# band-motor-feather.net
KiCad netlist of a schematic drawn in EAGLE
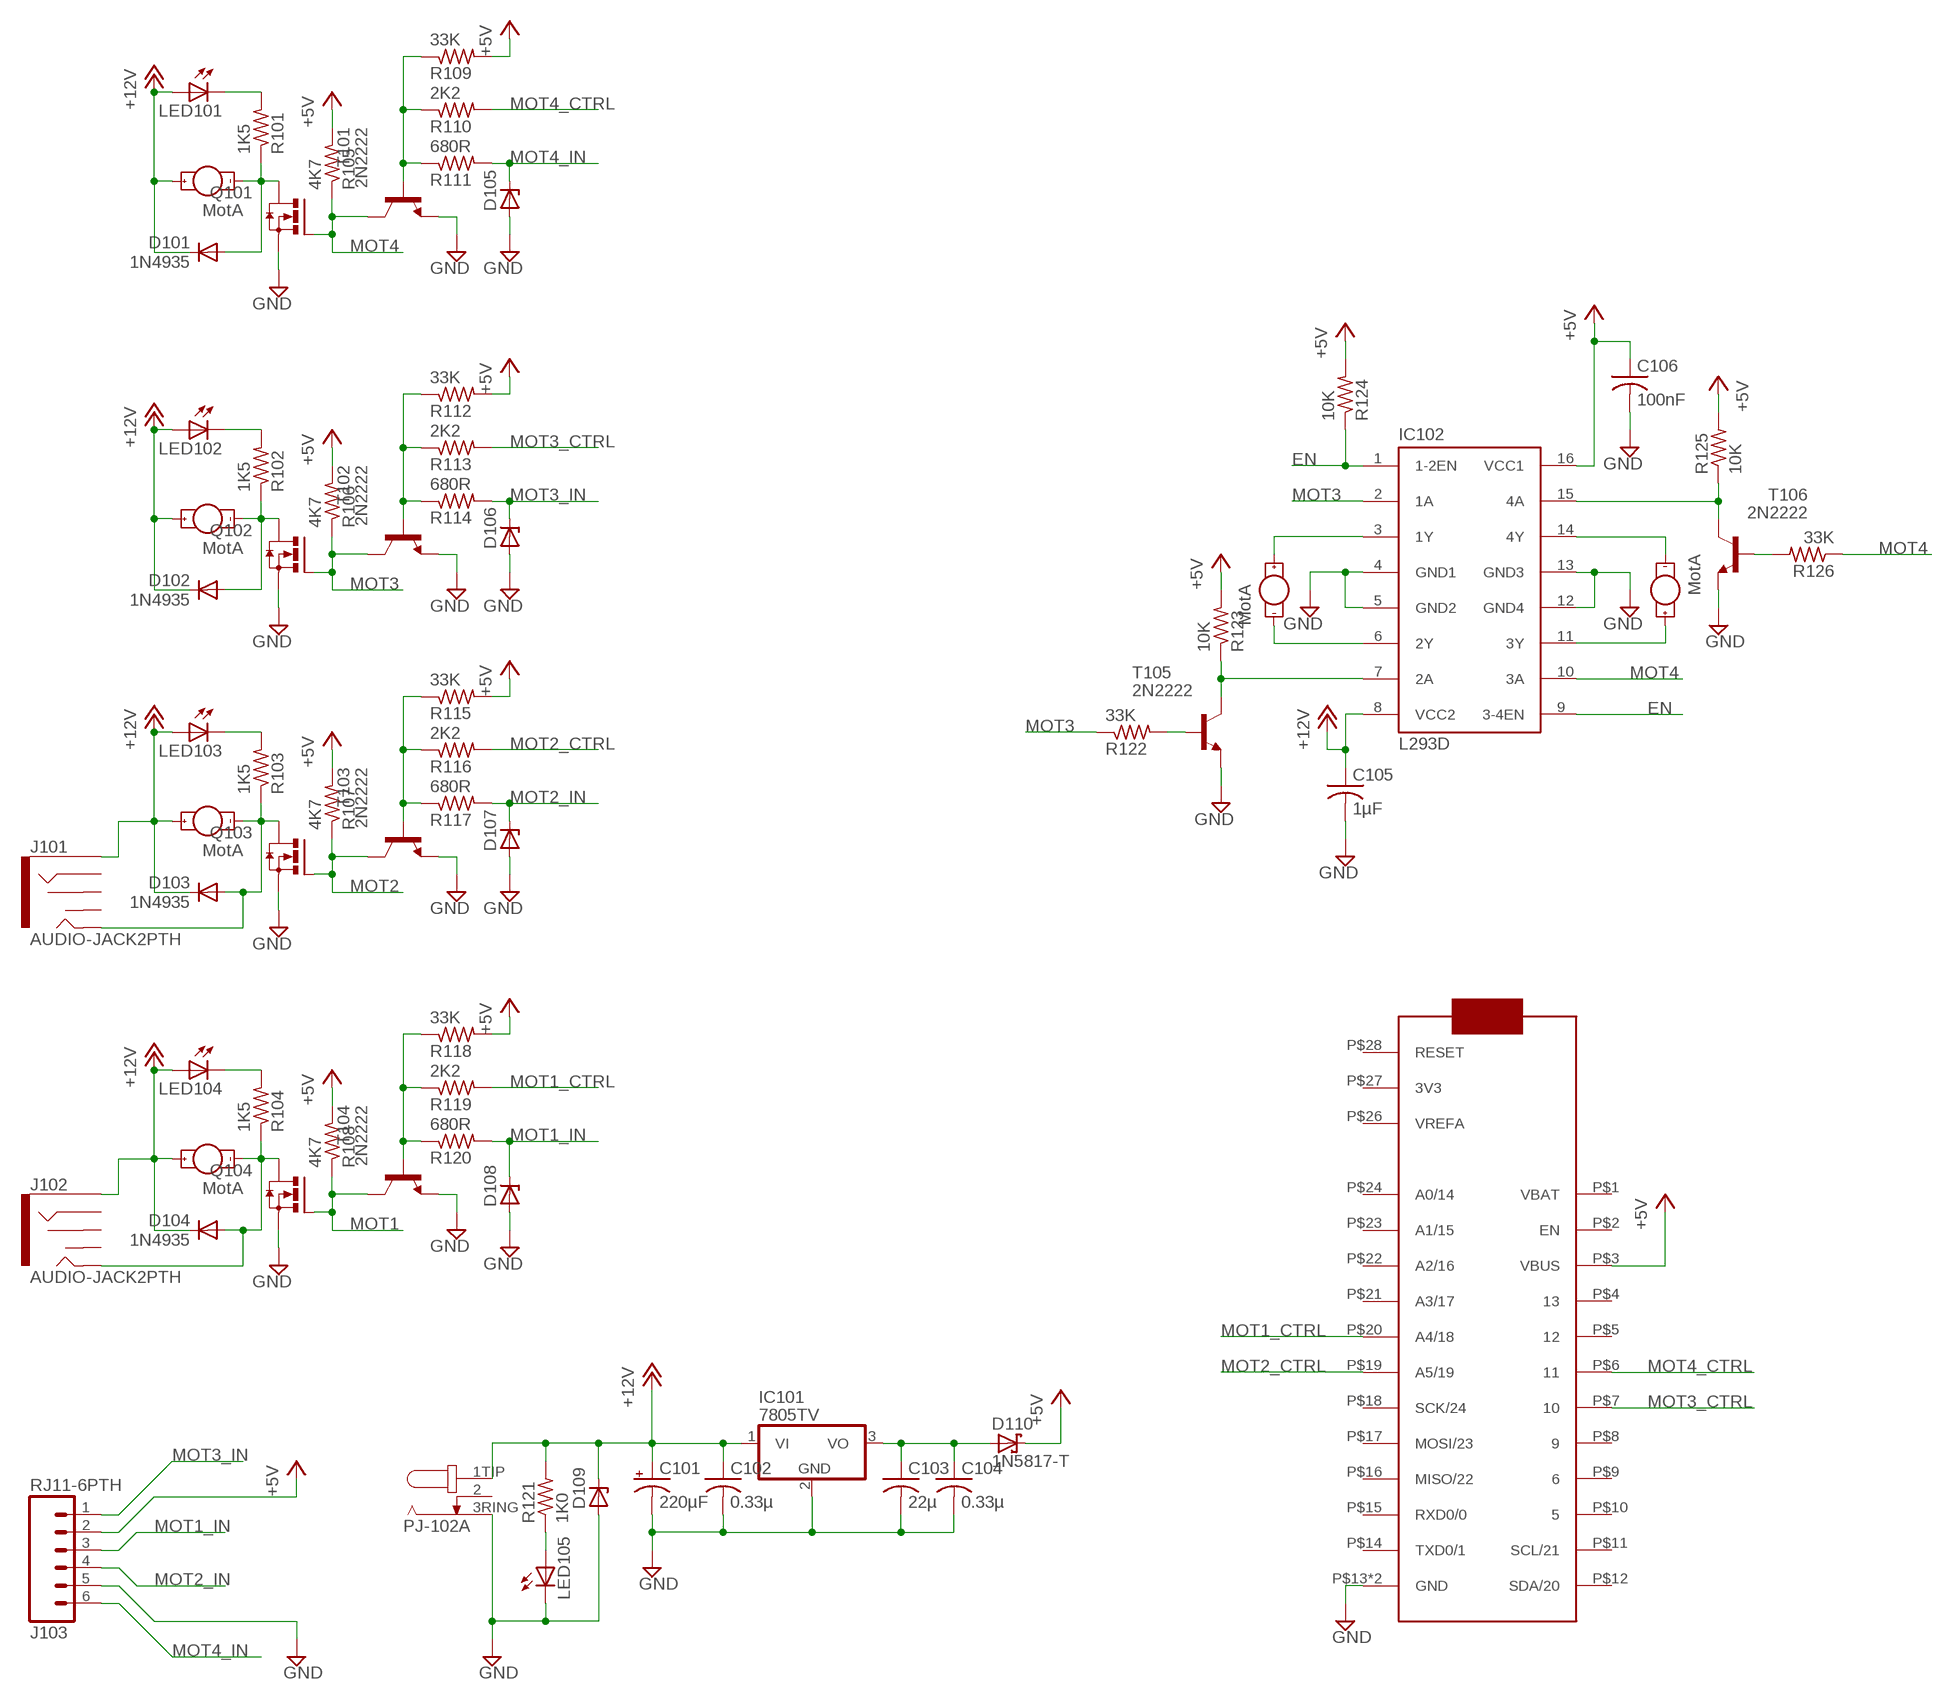
[diagram p0: schematic, sheet 1]

(export (version "E")
  (design (tool "Eeschema 10.0.6"))
  (components
    (comp (ref "C101")
      (value "220µF")
      (footprint "eagle-import:E3,5-8")
      (fields (field (name "MANF") "Panasonic Electronic Components"))
      (libsource (lib "eagle-import") (part "CPOL-USE3.5-8"))
    )
    (comp (ref "C102")
      (value "0.33µ")
      (footprint "eagle-import:C025-050X050")
      (fields (field (name "MANF") "TDK Corporation"))
      (libsource (lib "eagle-import") (part "C-US025-050X050"))
    )
    (comp (ref "C103")
      (value "22µ")
      (footprint "eagle-import:C050-045X075")
      (fields (field (name "MANF") "TDK Corporation"))
      (libsource (lib "eagle-import") (part "C-US050-045X075"))
    )
    (comp (ref "C104")
      (value "0.33µ")
      (footprint "eagle-import:C025-050X050")
      (fields (field (name "MANF") "TDK Corporation"))
      (libsource (lib "eagle-import") (part "C-US025-050X050"))
    )
    (comp (ref "C105")
      (value "1µF")
      (footprint "eagle-import:C025-025X050")
      (fields (field (name "MANF") "TDK Corporation"))
      (libsource (lib "eagle-import") (part "C-US025-025X050"))
    )
    (comp (ref "C106")
      (value "100nF")
      (footprint "eagle-import:C025-025X050")
      (fields (field (name "MANF") "Vishay BC Components"))
      (libsource (lib "eagle-import") (part "C-US025-025X050"))
    )
    (comp (ref "D101")
      (value "1N4935")
      (footprint "eagle-import:DO41-10")
      (fields (field (name "MANF") "Fairchild Semiconductor"))
      (libsource (lib "eagle-import") (part "1N4004"))
    )
    (comp (ref "D102")
      (value "1N4935")
      (footprint "eagle-import:DO41-10")
      (fields (field (name "MANF") "Fairchild Semiconductor"))
      (libsource (lib "eagle-import") (part "1N4004"))
    )
    (comp (ref "D103")
      (value "1N4935")
      (footprint "eagle-import:DO41-10")
      (fields (field (name "MANF") "Fairchild Semiconductor"))
      (libsource (lib "eagle-import") (part "1N4004"))
    )
    (comp (ref "D104")
      (value "1N4935")
      (footprint "eagle-import:DO41-10")
      (fields (field (name "MANF") "Fairchild Semiconductor"))
      (libsource (lib "eagle-import") (part "1N4004"))
    )
    (comp (ref "D105")
      (value "ZENER-DIODEF126-10")
      (footprint "eagle-import:F126Z10")
      (fields (field (name "MANF") "Littelfuse Inc."))
      (libsource (lib "eagle-import") (part "ZENER-DIODEF126-10"))
    )
    (comp (ref "D106")
      (value "ZENER-DIODEF126-10")
      (footprint "eagle-import:F126Z10")
      (fields (field (name "MANF") "Littelfuse Inc."))
      (libsource (lib "eagle-import") (part "ZENER-DIODEF126-10"))
    )
    (comp (ref "D107")
      (value "ZENER-DIODEF126-10")
      (footprint "eagle-import:F126Z10")
      (fields (field (name "MANF") "Littelfuse Inc."))
      (libsource (lib "eagle-import") (part "ZENER-DIODEF126-10"))
    )
    (comp (ref "D108")
      (value "ZENER-DIODEF126-10")
      (footprint "eagle-import:F126Z10")
      (fields (field (name "MANF") "Littelfuse Inc."))
      (libsource (lib "eagle-import") (part "ZENER-DIODEF126-10"))
    )
    (comp (ref "D109")
      (value "ZENER-DIODEF126-10")
      (footprint "eagle-import:F126Z10")
      (fields (field (name "MANF") "Littelfuse Inc."))
      (libsource (lib "eagle-import") (part "ZENER-DIODEF126-10"))
    )
    (comp (ref "D110")
      (value "1N5817-T")
      (footprint "eagle-import:DO41-7.6")
      (fields (field (name "MANF") "Fairchild Semiconductor"))
      (libsource (lib "eagle-import") (part "1N5817-T"))
    )
    (comp (ref "IC101")
      (value "7805TV")
      (footprint "eagle-import:TO220V")
      (fields (field (name "MANF") "Fairchild Semiconductor"))
      (libsource (lib "eagle-import") (part "78TV05"))
    )
    (comp (ref "IC102")
      (value "L293D")
      (footprint "eagle-import:DIL16")
      (fields (field (name "MANF") "Texas Instruments"))
      (libsource (lib "eagle-import") (part "L293D"))
    )
    (comp (ref "IC103")
      (value "FEATHER_M0")
      (footprint "eagle-import:FEATHER_M0")
      (fields (field (name "MANF") "Adafruit Industries LLC"))
      (libsource (lib "eagle-import") (part "FEATHER_M0"))
    )
    (comp (ref "J101")
      (value "AUDIO-JACK2PTH")
      (footprint "eagle-import:AUDIO-JACK")
      (fields (field (name "MANF") "CUI Inc."))
      (libsource (lib "eagle-import") (part "AUDIO-JACK2PTH"))
    )
    (comp (ref "J102")
      (value "AUDIO-JACK2PTH")
      (footprint "eagle-import:AUDIO-JACK")
      (fields (field (name "MANF") "CUI Inc."))
      (libsource (lib "eagle-import") (part "AUDIO-JACK2PTH"))
    )
    (comp (ref "J103")
      (value "RJ11-6PTH")
      (footprint "eagle-import:RJ11-6")
      (fields (field (name "MANF") "Assmann WSW Components"))
      (libsource (lib "eagle-import") (part "RJ11-6PTH"))
    )
    (comp (ref "J104")
      (value "MotA")
      (footprint "eagle-import:1X02_3.5MM_MOT")
      (fields (field (name "MANF") "On Shore Technology Inc."))
      (libsource (lib "eagle-import") (part "1X02_3.5MM_MOT"))
    )
    (comp (ref "J105")
      (value "MotA")
      (footprint "eagle-import:1X02_3.5MM_MOT")
      (fields (field (name "MANF") "On Shore Technology Inc."))
      (libsource (lib "eagle-import") (part "1X02_3.5MM_MOT"))
    )
    (comp (ref "J106")
      (value "MotA")
      (footprint "eagle-import:1X02_3.5MM_MOT")
      (fields (field (name "MANF") "On Shore Technology Inc."))
      (libsource (lib "eagle-import") (part "1X02_3.5MM_MOT"))
    )
    (comp (ref "J107")
      (value "MotA")
      (footprint "eagle-import:1X02_3.5MM_MOT")
      (fields (field (name "MANF") "On Shore Technology Inc."))
      (libsource (lib "eagle-import") (part "1X02_3.5MM_MOT"))
    )
    (comp (ref "J108")
      (value "PJ-102A")
      (footprint "eagle-import:PJ-102A")
      (fields (field (name "MANF") "CUI Inc."))
      (libsource (lib "eagle-import") (part "PJ-102A"))
    )
    (comp (ref "J109")
      (value "MotA")
      (footprint "eagle-import:1X02_3.5MM_MOT")
      (fields (field (name "MANF") "On Shore Technology Inc."))
      (libsource (lib "eagle-import") (part "1X02_3.5MM_MOT"))
    )
    (comp (ref "J110")
      (value "MotA")
      (footprint "eagle-import:1X02_3.5MM_MOT")
      (fields (field (name "MANF") "On Shore Technology Inc."))
      (libsource (lib "eagle-import") (part "1X02_3.5MM_MOT"))
    )
    (comp (ref "LED101")
      (value "LED3MM")
      (footprint "eagle-import:LED3MM")
      (fields (field (name "MANF") "Kingbright"))
      (libsource (lib "eagle-import") (part "LED3MM"))
    )
    (comp (ref "LED102")
      (value "LED3MM")
      (footprint "eagle-import:LED3MM")
      (fields (field (name "MANF") "Kingbright"))
      (libsource (lib "eagle-import") (part "LED3MM"))
    )
    (comp (ref "LED103")
      (value "LED3MM")
      (footprint "eagle-import:LED3MM")
      (fields (field (name "MANF") "Kingbright"))
      (libsource (lib "eagle-import") (part "LED3MM"))
    )
    (comp (ref "LED104")
      (value "LED3MM")
      (footprint "eagle-import:LED3MM")
      (fields (field (name "MANF") "Kingbright"))
      (libsource (lib "eagle-import") (part "LED3MM"))
    )
    (comp (ref "LED105")
      (value "LED5MM")
      (footprint "eagle-import:LED5MM")
      (fields (field (name "MANF") "Kingbright"))
      (libsource (lib "eagle-import") (part "LED5MM"))
    )
    (comp (ref "Q101")
      (value "IRLB8721")
      (footprint "eagle-import:TO220BV")
      (fields (field (name "MANF") "International Rectifier"))
      (libsource (lib "eagle-import") (part "IRLB8721"))
    )
    (comp (ref "Q102")
      (value "IRLB8721")
      (footprint "eagle-import:TO220BV")
      (fields (field (name "MANF") "International Rectifier"))
      (libsource (lib "eagle-import") (part "IRLB8721"))
    )
    (comp (ref "Q103")
      (value "IRLB8721")
      (footprint "eagle-import:TO220BV")
      (fields (field (name "MANF") "International Rectifier"))
      (libsource (lib "eagle-import") (part "IRLB8721"))
    )
    (comp (ref "Q104")
      (value "IRLB8721")
      (footprint "eagle-import:TO220BV")
      (fields (field (name "MANF") "International Rectifier"))
      (libsource (lib "eagle-import") (part "IRLB8721"))
    )
    (comp (ref "R101")
      (value "1K5")
      (footprint "eagle-import:0207_10")
      (fields (field (name "MANF") "Stackpole Electronics Inc"))
      (libsource (lib "eagle-import") (part "R-US_0207/10"))
    )
    (comp (ref "R102")
      (value "1K5")
      (footprint "eagle-import:0207_10")
      (fields (field (name "MANF") "Stackpole Electronics Inc"))
      (libsource (lib "eagle-import") (part "R-US_0207/10"))
    )
    (comp (ref "R103")
      (value "1K5")
      (footprint "eagle-import:0207_10")
      (fields (field (name "MANF") "Stackpole Electronics Inc"))
      (libsource (lib "eagle-import") (part "R-US_0207/10"))
    )
    (comp (ref "R104")
      (value "1K5")
      (footprint "eagle-import:0207_10")
      (fields (field (name "MANF") "Stackpole Electronics Inc"))
      (libsource (lib "eagle-import") (part "R-US_0207/10"))
    )
    (comp (ref "R105")
      (value "4K7")
      (footprint "eagle-import:0207_10")
      (fields (field (name "MANF") "Stackpole Electronics Inc"))
      (libsource (lib "eagle-import") (part "R-US_0207/10"))
    )
    (comp (ref "R106")
      (value "4K7")
      (footprint "eagle-import:0207_10")
      (fields (field (name "MANF") "Stackpole Electronics Inc"))
      (libsource (lib "eagle-import") (part "R-US_0207/10"))
    )
    (comp (ref "R107")
      (value "4K7")
      (footprint "eagle-import:0207_10")
      (fields (field (name "MANF") "Stackpole Electronics Inc"))
      (libsource (lib "eagle-import") (part "R-US_0207/10"))
    )
    (comp (ref "R108")
      (value "4K7")
      (footprint "eagle-import:0207_10")
      (fields (field (name "MANF") "Stackpole Electronics Inc"))
      (libsource (lib "eagle-import") (part "R-US_0207/10"))
    )
    (comp (ref "R109")
      (value "33K")
      (footprint "eagle-import:0207_10")
      (fields (field (name "MANF") "Stackpole Electronics Inc"))
      (libsource (lib "eagle-import") (part "R-US_0207/10"))
    )
    (comp (ref "R110")
      (value "2K2")
      (footprint "eagle-import:0207_10")
      (fields (field (name "MANF") "Stackpole Electronics Inc"))
      (libsource (lib "eagle-import") (part "R-US_0207/10"))
    )
    (comp (ref "R111")
      (value "680R")
      (footprint "eagle-import:0207_10")
      (fields (field (name "MANF") "Stackpole Electronics Inc"))
      (libsource (lib "eagle-import") (part "R-US_0207/10"))
    )
    (comp (ref "R112")
      (value "33K")
      (footprint "eagle-import:0207_10")
      (fields (field (name "MANF") "Stackpole Electronics Inc"))
      (libsource (lib "eagle-import") (part "R-US_0207/10"))
    )
    (comp (ref "R113")
      (value "2K2")
      (footprint "eagle-import:0207_10")
      (fields (field (name "MANF") "Stackpole Electronics Inc"))
      (libsource (lib "eagle-import") (part "R-US_0207/10"))
    )
    (comp (ref "R114")
      (value "680R")
      (footprint "eagle-import:0207_10")
      (fields (field (name "MANF") "Stackpole Electronics Inc"))
      (libsource (lib "eagle-import") (part "R-US_0207/10"))
    )
    (comp (ref "R115")
      (value "33K")
      (footprint "eagle-import:0207_10")
      (fields (field (name "MANF") "Stackpole Electronics Inc"))
      (libsource (lib "eagle-import") (part "R-US_0207/10"))
    )
    (comp (ref "R116")
      (value "2K2")
      (footprint "eagle-import:0207_10")
      (fields (field (name "MANF") "Stackpole Electronics Inc"))
      (libsource (lib "eagle-import") (part "R-US_0207/10"))
    )
    (comp (ref "R117")
      (value "680R")
      (footprint "eagle-import:0207_10")
      (fields (field (name "MANF") "Stackpole Electronics Inc"))
      (libsource (lib "eagle-import") (part "R-US_0207/10"))
    )
    (comp (ref "R118")
      (value "33K")
      (footprint "eagle-import:0207_10")
      (fields (field (name "MANF") "Stackpole Electronics Inc"))
      (libsource (lib "eagle-import") (part "R-US_0207/10"))
    )
    (comp (ref "R119")
      (value "2K2")
      (footprint "eagle-import:0207_10")
      (fields (field (name "MANF") "Stackpole Electronics Inc"))
      (libsource (lib "eagle-import") (part "R-US_0207/10"))
    )
    (comp (ref "R120")
      (value "680R")
      (footprint "eagle-import:0207_10")
      (fields (field (name "MANF") "Stackpole Electronics Inc"))
      (libsource (lib "eagle-import") (part "R-US_0207/10"))
    )
    (comp (ref "R121")
      (value "1K0")
      (footprint "eagle-import:0207_9")
      (fields (field (name "MANF") "Stackpole Electronics Inc."))
      (libsource (lib "eagle-import") (part "R-US_0207/9"))
    )
    (comp (ref "R122")
      (value "33K")
      (footprint "eagle-import:0207_10")
      (fields (field (name "MANF") "Stackpole Electronics Inc"))
      (libsource (lib "eagle-import") (part "R-US_0207/10"))
    )
    (comp (ref "R123")
      (value "10K")
      (footprint "eagle-import:0207_10")
      (fields (field (name "MANF") "Stackpole Electronics Inc"))
      (libsource (lib "eagle-import") (part "R-US_0207/10"))
    )
    (comp (ref "R124")
      (value "10K")
      (footprint "eagle-import:0207_10")
      (fields (field (name "MANF") "Stackpole Electronics Inc"))
      (libsource (lib "eagle-import") (part "R-US_0207/10"))
    )
    (comp (ref "R125")
      (value "10K")
      (footprint "eagle-import:0207_10")
      (fields (field (name "MANF") "Stackpole Electronics Inc"))
      (libsource (lib "eagle-import") (part "R-US_0207/10"))
    )
    (comp (ref "R126")
      (value "33K")
      (footprint "eagle-import:0207_10")
      (fields (field (name "MANF") "Stackpole Electronics Inc"))
      (libsource (lib "eagle-import") (part "R-US_0207/10"))
    )
    (comp (ref "T101")
      (value "2N2222")
      (footprint "eagle-import:TO92-EBC-OVAL")
      (fields (field (name "MANF") "Fairchild Semiconductor"))
      (libsource (lib "eagle-import") (part "2N2222"))
    )
    (comp (ref "T102")
      (value "2N2222")
      (footprint "eagle-import:TO92-EBC-OVAL")
      (fields (field (name "MANF") "Fairchild Semiconductor"))
      (libsource (lib "eagle-import") (part "2N2222"))
    )
    (comp (ref "T103")
      (value "2N2222")
      (footprint "eagle-import:TO92-EBC-OVAL")
      (fields (field (name "MANF") "Fairchild Semiconductor"))
      (libsource (lib "eagle-import") (part "2N2222"))
    )
    (comp (ref "T104")
      (value "2N2222")
      (footprint "eagle-import:TO92-EBC-OVAL")
      (fields (field (name "MANF") "Fairchild Semiconductor"))
      (libsource (lib "eagle-import") (part "2N2222"))
    )
    (comp (ref "T105")
      (value "2N2222")
      (footprint "eagle-import:TO92-EBC-OVAL")
      (fields (field (name "MANF") "Fairchild Semiconductor"))
      (libsource (lib "eagle-import") (part "2N2222"))
    )
    (comp (ref "T106")
      (value "2N2222")
      (footprint "eagle-import:TO92-EBC-OVAL")
      (fields (field (name "MANF") "Fairchild Semiconductor"))
      (libsource (lib "eagle-import") (part "2N2222"))
    )
  )
  (nets
    (net (code "1") (name "+5V") (class "Default")
      (node (ref "C106") (pin "1") (pinfunction "1_1") (pintype "passive"))
      (node (ref "D110") (pin "C") (pinfunction "C_C") (pintype "passive"))
      (node (ref "IC102") (pin "16") (pinfunction "VCC1_16") (pintype "power_in"))
      (node (ref "IC103") (pin "P$3") (pinfunction "VBUS_P$3") (pintype "bidirectional"))
      (node (ref "J103") (pin "2") (pinfunction "2_2") (pintype "passive"))
      (node (ref "R105") (pin "2") (pinfunction "2_2") (pintype "passive"))
      (node (ref "R106") (pin "2") (pinfunction "2_2") (pintype "passive"))
      (node (ref "R107") (pin "2") (pinfunction "2_2") (pintype "passive"))
      (node (ref "R108") (pin "2") (pinfunction "2_2") (pintype "passive"))
      (node (ref "R109") (pin "2") (pinfunction "2_2") (pintype "passive"))
      (node (ref "R112") (pin "2") (pinfunction "2_2") (pintype "passive"))
      (node (ref "R115") (pin "2") (pinfunction "2_2") (pintype "passive"))
      (node (ref "R118") (pin "2") (pinfunction "2_2") (pintype "passive"))
      (node (ref "R123") (pin "2") (pinfunction "2_2") (pintype "passive"))
      (node (ref "R124") (pin "2") (pinfunction "2_2") (pintype "passive"))
      (node (ref "R125") (pin "2") (pinfunction "2_2") (pintype "passive"))
    )
    (net (code "2") (name "+12V") (class "Default")
      (node (ref "C101") (pin "+") (pinfunction "+_+") (pintype "passive"))
      (node (ref "C102") (pin "1") (pinfunction "1_1") (pintype "passive"))
      (node (ref "C105") (pin "1") (pinfunction "1_1") (pintype "passive"))
      (node (ref "D101") (pin "C") (pinfunction "C_C") (pintype "passive"))
      (node (ref "D102") (pin "C") (pinfunction "C_C") (pintype "passive"))
      (node (ref "D103") (pin "C") (pinfunction "C_C") (pintype "passive"))
      (node (ref "D104") (pin "C") (pinfunction "C_C") (pintype "passive"))
      (node (ref "D109") (pin "C") (pinfunction "C_C") (pintype "passive"))
      (node (ref "IC101") (pin "1") (pinfunction "VI_1") (pintype "input"))
      (node (ref "IC102") (pin "8") (pinfunction "VCC2_8") (pintype "power_in"))
      (node (ref "J101") (pin "SLEEVE") (pinfunction "SLEEVE_SLEEVE") (pintype "bidirectional"))
      (node (ref "J102") (pin "SLEEVE") (pinfunction "SLEEVE_SLEEVE") (pintype "bidirectional"))
      (node (ref "J104") (pin "1A") (pinfunction "+_1A") (pintype "bidirectional"))
      (node (ref "J105") (pin "1A") (pinfunction "+_1A") (pintype "bidirectional"))
      (node (ref "J106") (pin "1A") (pinfunction "+_1A") (pintype "bidirectional"))
      (node (ref "J107") (pin "1A") (pinfunction "+_1A") (pintype "bidirectional"))
      (node (ref "J108") (pin "1TIP") (pinfunction "3TIP_1TIP") (pintype "passive"))
      (node (ref "LED101") (pin "A") (pinfunction "A_A") (pintype "passive"))
      (node (ref "LED102") (pin "A") (pinfunction "A_A") (pintype "passive"))
      (node (ref "LED103") (pin "A") (pinfunction "A_A") (pintype "passive"))
      (node (ref "LED104") (pin "A") (pinfunction "A_A") (pintype "passive"))
      (node (ref "R121") (pin "2") (pinfunction "2_2") (pintype "passive"))
    )
    (net (code "3") (name "/EN") (class "Default")
      (node (ref "IC102") (pin "1") (pinfunction "1-2EN_1") (pintype "input"))
      (node (ref "IC102") (pin "9") (pinfunction "3-4EN_9") (pintype "input"))
      (node (ref "R124") (pin "1") (pinfunction "1_1") (pintype "passive"))
    )
    (net (code "4") (name "/MOT1") (class "Default")
      (node (ref "Q104") (pin "G") (pinfunction "G_G") (pintype "passive"))
      (node (ref "R108") (pin "1") (pinfunction "1_1") (pintype "passive"))
      (node (ref "T104") (pin "C") (pinfunction "C_C") (pintype "passive"))
    )
    (net (code "5") (name "/MOT1_CTRL") (class "Default")
      (node (ref "IC103") (pin "P$20") (pinfunction "A4/18_P$20") (pintype "bidirectional"))
      (node (ref "R119") (pin "2") (pinfunction "2_2") (pintype "passive"))
    )
    (net (code "6") (name "/MOT1_IN") (class "Default")
      (node (ref "D108") (pin "C") (pinfunction "C_C") (pintype "passive"))
      (node (ref "J103") (pin "3") (pinfunction "3_3") (pintype "passive"))
      (node (ref "R120") (pin "2") (pinfunction "2_2") (pintype "passive"))
    )
    (net (code "7") (name "/MOT2") (class "Default")
      (node (ref "Q103") (pin "G") (pinfunction "G_G") (pintype "passive"))
      (node (ref "R107") (pin "1") (pinfunction "1_1") (pintype "passive"))
      (node (ref "T103") (pin "C") (pinfunction "C_C") (pintype "passive"))
    )
    (net (code "8") (name "/MOT2_CTRL") (class "Default")
      (node (ref "IC103") (pin "P$19") (pinfunction "A5/19_P$19") (pintype "bidirectional"))
      (node (ref "R116") (pin "2") (pinfunction "2_2") (pintype "passive"))
    )
    (net (code "9") (name "/MOT2_IN") (class "Default")
      (node (ref "D107") (pin "C") (pinfunction "C_C") (pintype "passive"))
      (node (ref "J103") (pin "4") (pinfunction "4_4") (pintype "passive"))
      (node (ref "R117") (pin "2") (pinfunction "2_2") (pintype "passive"))
    )
    (net (code "10") (name "/MOT3") (class "Default")
      (node (ref "IC102") (pin "2") (pinfunction "1A_2") (pintype "input"))
      (node (ref "Q102") (pin "G") (pinfunction "G_G") (pintype "passive"))
      (node (ref "R106") (pin "1") (pinfunction "1_1") (pintype "passive"))
      (node (ref "R122") (pin "1") (pinfunction "1_1") (pintype "passive"))
      (node (ref "T102") (pin "C") (pinfunction "C_C") (pintype "passive"))
    )
    (net (code "11") (name "/MOT3_CTRL") (class "Default")
      (node (ref "IC103") (pin "P$7") (pinfunction "10_P$7") (pintype "bidirectional"))
      (node (ref "R113") (pin "2") (pinfunction "2_2") (pintype "passive"))
    )
    (net (code "12") (name "/MOT3_IN") (class "Default")
      (node (ref "D106") (pin "C") (pinfunction "C_C") (pintype "passive"))
      (node (ref "J103") (pin "1") (pinfunction "1_1") (pintype "passive"))
      (node (ref "R114") (pin "2") (pinfunction "2_2") (pintype "passive"))
    )
    (net (code "13") (name "/MOT4") (class "Default")
      (node (ref "IC102") (pin "10") (pinfunction "3A_10") (pintype "input"))
      (node (ref "Q101") (pin "G") (pinfunction "G_G") (pintype "passive"))
      (node (ref "R105") (pin "1") (pinfunction "1_1") (pintype "passive"))
      (node (ref "R126") (pin "1") (pinfunction "1_1") (pintype "passive"))
      (node (ref "T101") (pin "C") (pinfunction "C_C") (pintype "passive"))
    )
    (net (code "14") (name "/MOT4_CTRL") (class "Default")
      (node (ref "IC103") (pin "P$6") (pinfunction "11_P$6") (pintype "bidirectional"))
      (node (ref "R110") (pin "2") (pinfunction "2_2") (pintype "passive"))
    )
    (net (code "15") (name "/MOT4_IN") (class "Default")
      (node (ref "D105") (pin "C") (pinfunction "C_C") (pintype "passive"))
      (node (ref "J103") (pin "6") (pinfunction "6_6") (pintype "passive"))
      (node (ref "R111") (pin "2") (pinfunction "2_2") (pintype "passive"))
    )
    (net (code "16") (name "GND") (class "Default")
      (node (ref "C101") (pin "-") (pinfunction "-_-") (pintype "passive"))
      (node (ref "C102") (pin "2") (pinfunction "2_2") (pintype "passive"))
      (node (ref "C103") (pin "2") (pinfunction "2_2") (pintype "passive"))
      (node (ref "C104") (pin "2") (pinfunction "2_2") (pintype "passive"))
      (node (ref "C105") (pin "2") (pinfunction "2_2") (pintype "passive"))
      (node (ref "C106") (pin "2") (pinfunction "2_2") (pintype "passive"))
      (node (ref "D105") (pin "A") (pinfunction "A_A") (pintype "passive"))
      (node (ref "D106") (pin "A") (pinfunction "A_A") (pintype "passive"))
      (node (ref "D107") (pin "A") (pinfunction "A_A") (pintype "passive"))
      (node (ref "D108") (pin "A") (pinfunction "A_A") (pintype "passive"))
      (node (ref "D109") (pin "A") (pinfunction "A_A") (pintype "passive"))
      (node (ref "IC101") (pin "2") (pinfunction "GND_2") (pintype "passive"))
      (node (ref "IC102") (pin "12") (pinfunction "GND4_12") (pintype "power_in"))
      (node (ref "IC102") (pin "13") (pinfunction "GND3_13") (pintype "power_in"))
      (node (ref "IC102") (pin "4") (pinfunction "GND1_4") (pintype "power_in"))
      (node (ref "IC102") (pin "5") (pinfunction "GND2_5") (pintype "power_in"))
      (node (ref "IC103") (pin "P$13") (pinfunction "GND_P$13") (pintype "bidirectional"))
      (node (ref "IC103") (pin "P$25") (pinfunction "GND_P$25") (pintype "bidirectional"))
      (node (ref "J103") (pin "5") (pinfunction "5_5") (pintype "passive"))
      (node (ref "J108") (pin "3RING") (pinfunction "1RING_3RING") (pintype "passive"))
      (node (ref "LED105") (pin "K") (pinfunction "C_K") (pintype "passive"))
      (node (ref "Q101") (pin "S") (pinfunction "S_S") (pintype "passive"))
      (node (ref "Q102") (pin "S") (pinfunction "S_S") (pintype "passive"))
      (node (ref "Q103") (pin "S") (pinfunction "S_S") (pintype "passive"))
      (node (ref "Q104") (pin "S") (pinfunction "S_S") (pintype "passive"))
      (node (ref "T101") (pin "E") (pinfunction "E_E") (pintype "passive"))
      (node (ref "T102") (pin "E") (pinfunction "E_E") (pintype "passive"))
      (node (ref "T103") (pin "E") (pinfunction "E_E") (pintype "passive"))
      (node (ref "T104") (pin "E") (pinfunction "E_E") (pintype "passive"))
      (node (ref "T105") (pin "E") (pinfunction "E_E") (pintype "passive"))
      (node (ref "T106") (pin "E") (pinfunction "E_E") (pintype "passive"))
    )
    (net (code "17") (name "Net-(IC101-VO)") (class "Default")
      (node (ref "C103") (pin "1") (pinfunction "1_1") (pintype "passive"))
      (node (ref "C104") (pin "1") (pinfunction "1_1") (pintype "passive"))
      (node (ref "D110") (pin "A") (pinfunction "A_A") (pintype "passive"))
      (node (ref "IC101") (pin "3") (pinfunction "VO_3") (pintype "passive"))
    )
    (net (code "18") (name "Net-(IC102-1Y)") (class "Default")
      (node (ref "IC102") (pin "3") (pinfunction "1Y_3") (pintype "output"))
      (node (ref "J109") (pin "1A") (pinfunction "+_1A") (pintype "bidirectional"))
    )
    (net (code "19") (name "Net-(IC102-2A)") (class "Default")
      (node (ref "IC102") (pin "7") (pinfunction "2A_7") (pintype "input"))
      (node (ref "R123") (pin "1") (pinfunction "1_1") (pintype "passive"))
      (node (ref "T105") (pin "C") (pinfunction "C_C") (pintype "passive"))
    )
    (net (code "20") (name "Net-(IC102-2Y)") (class "Default")
      (node (ref "IC102") (pin "6") (pinfunction "2Y_6") (pintype "output"))
      (node (ref "J109") (pin "2K") (pinfunction "-_2K") (pintype "bidirectional"))
    )
    (net (code "21") (name "Net-(IC102-3Y)") (class "Default")
      (node (ref "IC102") (pin "11") (pinfunction "3Y_11") (pintype "output"))
      (node (ref "J110") (pin "1A") (pinfunction "+_1A") (pintype "bidirectional"))
    )
    (net (code "22") (name "Net-(IC102-4A)") (class "Default")
      (node (ref "IC102") (pin "15") (pinfunction "4A_15") (pintype "input"))
      (node (ref "R125") (pin "1") (pinfunction "1_1") (pintype "passive"))
      (node (ref "T106") (pin "C") (pinfunction "C_C") (pintype "passive"))
    )
    (net (code "23") (name "Net-(IC102-4Y)") (class "Default")
      (node (ref "IC102") (pin "14") (pinfunction "4Y_14") (pintype "output"))
      (node (ref "J110") (pin "2K") (pinfunction "-_2K") (pintype "bidirectional"))
    )
    (net (code "24") (name "Net-(J104--)") (class "Default")
      (node (ref "D101") (pin "A") (pinfunction "A_A") (pintype "passive"))
      (node (ref "J104") (pin "2K") (pinfunction "-_2K") (pintype "bidirectional"))
      (node (ref "Q101") (pin "D") (pinfunction "D_D") (pintype "passive"))
      (node (ref "R101") (pin "1") (pinfunction "1_1") (pintype "passive"))
    )
    (net (code "25") (name "Net-(J105--)") (class "Default")
      (node (ref "D102") (pin "A") (pinfunction "A_A") (pintype "passive"))
      (node (ref "J105") (pin "2K") (pinfunction "-_2K") (pintype "bidirectional"))
      (node (ref "Q102") (pin "D") (pinfunction "D_D") (pintype "passive"))
      (node (ref "R102") (pin "1") (pinfunction "1_1") (pintype "passive"))
    )
    (net (code "26") (name "Net-(J106--)") (class "Default")
      (node (ref "D103") (pin "A") (pinfunction "A_A") (pintype "passive"))
      (node (ref "J101") (pin "TIP") (pinfunction "TIP_TIP") (pintype "bidirectional"))
      (node (ref "J106") (pin "2K") (pinfunction "-_2K") (pintype "bidirectional"))
      (node (ref "Q103") (pin "D") (pinfunction "D_D") (pintype "passive"))
      (node (ref "R103") (pin "1") (pinfunction "1_1") (pintype "passive"))
    )
    (net (code "27") (name "Net-(J107--)") (class "Default")
      (node (ref "D104") (pin "A") (pinfunction "A_A") (pintype "passive"))
      (node (ref "J102") (pin "TIP") (pinfunction "TIP_TIP") (pintype "bidirectional"))
      (node (ref "J107") (pin "2K") (pinfunction "-_2K") (pintype "bidirectional"))
      (node (ref "Q104") (pin "D") (pinfunction "D_D") (pintype "passive"))
      (node (ref "R104") (pin "1") (pinfunction "1_1") (pintype "passive"))
    )
    (net (code "28") (name "Net-(LED101-C)") (class "Default")
      (node (ref "LED101") (pin "K") (pinfunction "C_K") (pintype "passive"))
      (node (ref "R101") (pin "2") (pinfunction "2_2") (pintype "passive"))
    )
    (net (code "29") (name "Net-(LED102-C)") (class "Default")
      (node (ref "LED102") (pin "K") (pinfunction "C_K") (pintype "passive"))
      (node (ref "R102") (pin "2") (pinfunction "2_2") (pintype "passive"))
    )
    (net (code "30") (name "Net-(LED103-C)") (class "Default")
      (node (ref "LED103") (pin "K") (pinfunction "C_K") (pintype "passive"))
      (node (ref "R103") (pin "2") (pinfunction "2_2") (pintype "passive"))
    )
    (net (code "31") (name "Net-(LED104-C)") (class "Default")
      (node (ref "LED104") (pin "K") (pinfunction "C_K") (pintype "passive"))
      (node (ref "R104") (pin "2") (pinfunction "2_2") (pintype "passive"))
    )
    (net (code "32") (name "Net-(LED105-PadA)") (class "Default")
      (node (ref "LED105") (pin "A") (pinfunction "A_A") (pintype "passive"))
      (node (ref "R121") (pin "1") (pinfunction "1_1") (pintype "passive"))
    )
    (net (code "33") (name "Net-(R109-Pad1)") (class "Default")
      (node (ref "R109") (pin "1") (pinfunction "1_1") (pintype "passive"))
      (node (ref "R110") (pin "1") (pinfunction "1_1") (pintype "passive"))
      (node (ref "R111") (pin "1") (pinfunction "1_1") (pintype "passive"))
      (node (ref "T101") (pin "B") (pinfunction "B_B") (pintype "passive"))
    )
    (net (code "34") (name "Net-(R112-Pad1)") (class "Default")
      (node (ref "R112") (pin "1") (pinfunction "1_1") (pintype "passive"))
      (node (ref "R113") (pin "1") (pinfunction "1_1") (pintype "passive"))
      (node (ref "R114") (pin "1") (pinfunction "1_1") (pintype "passive"))
      (node (ref "T102") (pin "B") (pinfunction "B_B") (pintype "passive"))
    )
    (net (code "35") (name "Net-(R115-Pad1)") (class "Default")
      (node (ref "R115") (pin "1") (pinfunction "1_1") (pintype "passive"))
      (node (ref "R116") (pin "1") (pinfunction "1_1") (pintype "passive"))
      (node (ref "R117") (pin "1") (pinfunction "1_1") (pintype "passive"))
      (node (ref "T103") (pin "B") (pinfunction "B_B") (pintype "passive"))
    )
    (net (code "36") (name "Net-(R118-Pad1)") (class "Default")
      (node (ref "R118") (pin "1") (pinfunction "1_1") (pintype "passive"))
      (node (ref "R119") (pin "1") (pinfunction "1_1") (pintype "passive"))
      (node (ref "R120") (pin "1") (pinfunction "1_1") (pintype "passive"))
      (node (ref "T104") (pin "B") (pinfunction "B_B") (pintype "passive"))
    )
    (net (code "37") (name "Net-(R122-Pad2)") (class "Default")
      (node (ref "R122") (pin "2") (pinfunction "2_2") (pintype "passive"))
      (node (ref "T105") (pin "B") (pinfunction "B_B") (pintype "passive"))
    )
    (net (code "38") (name "Net-(R126-Pad2)") (class "Default")
      (node (ref "R126") (pin "2") (pinfunction "2_2") (pintype "passive"))
      (node (ref "T106") (pin "B") (pinfunction "B_B") (pintype "passive"))
    )
    (net (code "39") (name "unconnected-(IC103-3V3-PadP$27)") (class "Default")
      (node (ref "IC103") (pin "P$27") (pinfunction "3V3_P$27") (pintype "bidirectional"))
    )
    (net (code "40") (name "unconnected-(IC103-5-PadP$10)") (class "Default")
      (node (ref "IC103") (pin "P$10") (pinfunction "5_P$10") (pintype "bidirectional"))
    )
    (net (code "41") (name "unconnected-(IC103-6-PadP$9)") (class "Default")
      (node (ref "IC103") (pin "P$9") (pinfunction "6_P$9") (pintype "bidirectional"))
    )
    (net (code "42") (name "unconnected-(IC103-9-PadP$8)") (class "Default")
      (node (ref "IC103") (pin "P$8") (pinfunction "9_P$8") (pintype "bidirectional"))
    )
    (net (code "43") (name "unconnected-(IC103-12-PadP$5)") (class "Default")
      (node (ref "IC103") (pin "P$5") (pinfunction "12_P$5") (pintype "bidirectional"))
    )
    (net (code "44") (name "unconnected-(IC103-13-PadP$4)") (class "Default")
      (node (ref "IC103") (pin "P$4") (pinfunction "13_P$4") (pintype "bidirectional"))
    )
    (net (code "45") (name "unconnected-(IC103-A0{slash}14-PadP$24)") (class "Default")
      (node (ref "IC103") (pin "P$24") (pinfunction "A0/14_P$24") (pintype "bidirectional"))
    )
    (net (code "46") (name "unconnected-(IC103-A1{slash}15-PadP$23)") (class "Default")
      (node (ref "IC103") (pin "P$23") (pinfunction "A1/15_P$23") (pintype "bidirectional"))
    )
    (net (code "47") (name "unconnected-(IC103-A2{slash}16-PadP$22)") (class "Default")
      (node (ref "IC103") (pin "P$22") (pinfunction "A2/16_P$22") (pintype "bidirectional"))
    )
    (net (code "48") (name "unconnected-(IC103-A3{slash}17-PadP$21)") (class "Default")
      (node (ref "IC103") (pin "P$21") (pinfunction "A3/17_P$21") (pintype "bidirectional"))
    )
    (net (code "49") (name "unconnected-(IC103-EN-PadP$2)") (class "Default")
      (node (ref "IC103") (pin "P$2") (pinfunction "EN_P$2") (pintype "bidirectional"))
    )
    (net (code "50") (name "unconnected-(IC103-MISO{slash}22-PadP$16)") (class "Default")
      (node (ref "IC103") (pin "P$16") (pinfunction "MISO/22_P$16") (pintype "bidirectional"))
    )
    (net (code "51") (name "unconnected-(IC103-MOSI{slash}23-PadP$17)") (class "Default")
      (node (ref "IC103") (pin "P$17") (pinfunction "MOSI/23_P$17") (pintype "bidirectional"))
    )
    (net (code "52") (name "unconnected-(IC103-RESET-PadP$28)") (class "Default")
      (node (ref "IC103") (pin "P$28") (pinfunction "RESET_P$28") (pintype "bidirectional"))
    )
    (net (code "53") (name "unconnected-(IC103-RXD0{slash}0-PadP$15)") (class "Default")
      (node (ref "IC103") (pin "P$15") (pinfunction "RXD0/0_P$15") (pintype "bidirectional"))
    )
    (net (code "54") (name "unconnected-(IC103-SCK{slash}24-PadP$18)") (class "Default")
      (node (ref "IC103") (pin "P$18") (pinfunction "SCK/24_P$18") (pintype "bidirectional"))
    )
    (net (code "55") (name "unconnected-(IC103-SCL{slash}21-PadP$11)") (class "Default")
      (node (ref "IC103") (pin "P$11") (pinfunction "SCL/21_P$11") (pintype "bidirectional"))
    )
    (net (code "56") (name "unconnected-(IC103-SDA{slash}20-PadP$12)") (class "Default")
      (node (ref "IC103") (pin "P$12") (pinfunction "SDA/20_P$12") (pintype "bidirectional"))
    )
    (net (code "57") (name "unconnected-(IC103-TXD0{slash}1-PadP$14)") (class "Default")
      (node (ref "IC103") (pin "P$14") (pinfunction "TXD0/1_P$14") (pintype "bidirectional"))
    )
    (net (code "58") (name "unconnected-(IC103-VBAT-PadP$1)") (class "Default")
      (node (ref "IC103") (pin "P$1") (pinfunction "VBAT_P$1") (pintype "bidirectional"))
    )
    (net (code "59") (name "unconnected-(IC103-VREFA-PadP$26)") (class "Default")
      (node (ref "IC103") (pin "P$26") (pinfunction "VREFA_P$26") (pintype "bidirectional"))
    )
    (net (code "60") (name "unconnected-(J101-PadRING)") (class "Default")
      (node (ref "J101") (pin "RING") (pinfunction "RING_RING") (pintype "bidirectional"))
    )
    (net (code "61") (name "unconnected-(J101-PadRSH)") (class "Default")
      (node (ref "J101") (pin "RSH") (pinfunction "RSH_RSH") (pintype "bidirectional"))
    )
    (net (code "62") (name "unconnected-(J101-PadTSH)") (class "Default")
      (node (ref "J101") (pin "TSH") (pinfunction "TSH_TSH") (pintype "bidirectional"))
    )
    (net (code "63") (name "unconnected-(J102-PadRING)") (class "Default")
      (node (ref "J102") (pin "RING") (pinfunction "RING_RING") (pintype "bidirectional"))
    )
    (net (code "64") (name "unconnected-(J102-PadRSH)") (class "Default")
      (node (ref "J102") (pin "RSH") (pinfunction "RSH_RSH") (pintype "bidirectional"))
    )
    (net (code "65") (name "unconnected-(J102-PadTSH)") (class "Default")
      (node (ref "J102") (pin "TSH") (pinfunction "TSH_TSH") (pintype "bidirectional"))
    )
    (net (code "66") (name "unconnected-(J108-Pad2)") (class "Default")
      (node (ref "J108") (pin "2") (pinfunction "2_2") (pintype "passive"))
    )
  )
)
